# Half_H-Bridge_Driver.net
KiCad netlist of a schematic drawn in Altium Designer
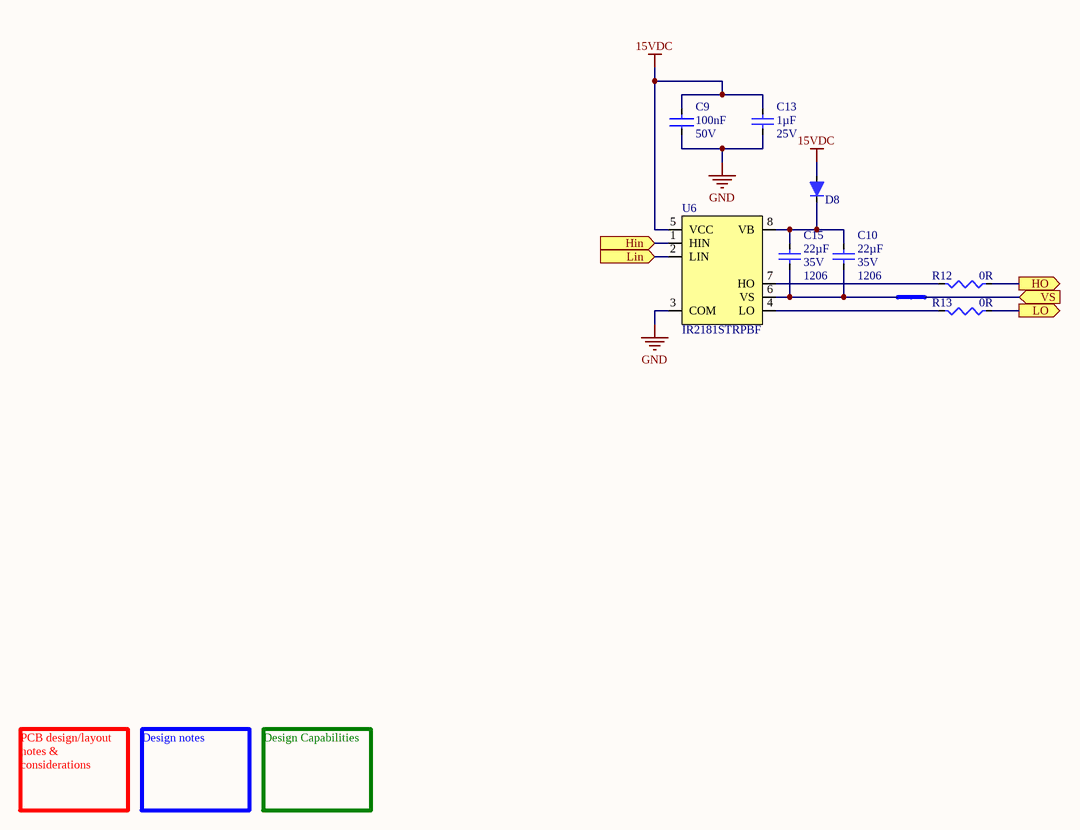
[diagram p0: Half H-Bridge Driver.SchDoc]

(export (version "E")
  (design (tool "Eeschema 10.0.6"))
  (components
    (comp (ref "C9")
      (value "100nF 0603 50V")
      (footprint "C0603 - Ceramic")
      (fields
        (field (name "MANUFACTURER") "Samsung Electro-Mechanics America, Inc")
        (field (name "MANUFACTURER PART NUMBER") "CL10B104KB8SFNC")
        (field (name "TOLERANCE") "±10%")
        (field (name "VOLTAGE - RATED") "50V")
        (field (name "CAPACITANCE") "100nF")
      )
      (libsource (lib "Personal Library") (part "100nF 0603 50V"))
    )
    (comp (ref "C10")
      (value "22uF 1206 35V")
      (description "Non-polarized")
      (fields
        (field (name "MANUFACTURER") "TDK Corporation")
        (field (name "MANUFACTURER PART NUMBER") "C3216X5R1V226M160AC")
        (field (name "CAPACITANCE") "22µF")
        (field (name "VOLTAGE - RATED") "35V")
        (field (name "PACKAGE / CASE") "1206")
      )
      (libsource (lib "Local Library") (part "22uF 1206 35V"))
    )
    (comp (ref "C13")
      (value "1uF 0603 25V")
      (footprint "Capacitor - 0603 Ceramic")
      (description "Non-polarized")
      (fields
        (field (name "MANUFACTURER") "Murata Electronics North America")
        (field (name "MANUFACTURER PART NUMBER") "GRM188R61E105KA12D")
        (field (name "VOLTAGE - RATED") "25V")
        (field (name "CAPACITANCE") "1µF")
      )
      (libsource (lib "Local Library") (part "1uF 0603 25V"))
    )
    (comp (ref "C15")
      (value "22uF 1206 35V")
      (description "Non-polarized")
      (fields
        (field (name "MANUFACTURER") "TDK Corporation")
        (field (name "MANUFACTURER PART NUMBER") "C3216X5R1V226M160AC")
        (field (name "VOLTAGE - RATED") "35V")
        (field (name "PACKAGE / CASE") "1206")
        (field (name "CAPACITANCE") "22µF")
      )
      (libsource (lib "Local Library") (part "22uF 1206 35V"))
    )
    (comp (ref "D8")
      (value "~")
      (description "Signal Diode")
      (fields
        (field (name "MANUFACTURER") "Vishay Semiconductor Diodes Division")
        (field (name "MANUFACTURER PART NUMBER") "US1G-E3/5AT")
      )
      (libsource (lib "Local Library") (part "Diode - Signal 1A"))
    )
    (comp (ref "NetTie1")
      (value "Net Tie - Same Size")
      (description "Ties two nets together")
      (libsource (lib "Local Library") (part "Net Tie - Same Size"))
    )
    (comp (ref "R12")
      (value "0R 0603")
      (footprint "R0603")
      (fields
        (field (name "MANUFACTURER") "Yageo")
        (field (name "MANUFACTURER PART NUMBER") "RC0603JR-070RL")
        (field (name "RESISTANCE (OHMS)") "0R")
        (field (name "TOLERANCE") "Jumper")
      )
      (libsource (lib "Local Library") (part "0R 0603"))
    )
    (comp (ref "R13")
      (value "0R 0603")
      (footprint "R0603")
      (fields
        (field (name "MANUFACTURER") "Yageo")
        (field (name "MANUFACTURER PART NUMBER") "RC0603JR-070RL")
        (field (name "RESISTANCE (OHMS)") "0R")
        (field (name "TOLERANCE") "Jumper")
      )
      (libsource (lib "Local Library") (part "0R 0603"))
    )
    (comp (ref "U6")
      (value "H-Bridge Driver")
      (footprint "SOIC-8")
      (fields
        (field (name "MANUFACTURER") "Infineon Technologies")
        (field (name "MANUFACTURER PART NUMBER") "IR2181STRPBF")
      )
      (libsource (lib "Local Library") (part "H-Bridge Driver"))
    )
  )
  (nets
    (net (code "1") (name "/HO") (class "Default")
      (node (ref "R12") (pin "2") (pinfunction "2_2") (pintype "passive"))
    )
    (net (code "2") (name "/Hin") (class "Default")
      (node (ref "U6") (pin "1") (pinfunction "HIN_1") (pintype "passive"))
    )
    (net (code "3") (name "/LO") (class "Default")
      (node (ref "R13") (pin "2") (pinfunction "2_2") (pintype "passive"))
    )
    (net (code "4") (name "/Lin") (class "Default")
      (node (ref "U6") (pin "2") (pinfunction "LIN_2") (pintype "passive"))
    )
    (net (code "5") (name "/VS") (class "Default")
      (node (ref "NetTie1") (pin "1") (pinfunction "1_1") (pintype "passive"))
    )
    (net (code "6") (name "15VDC") (class "Default")
      (node (ref "C13") (pin "1") (pinfunction "1_1") (pintype "passive"))
      (node (ref "C9") (pin "1") (pinfunction "1_1") (pintype "passive"))
      (node (ref "D8") (pin "1") (pinfunction "Anode_1") (pintype "passive"))
      (node (ref "U6") (pin "5") (pinfunction "VCC_5") (pintype "passive"))
    )
    (net (code "7") (name "GND") (class "Default")
      (node (ref "C13") (pin "2") (pinfunction "2_2") (pintype "passive"))
      (node (ref "C9") (pin "2") (pinfunction "2_2") (pintype "passive"))
      (node (ref "U6") (pin "3") (pinfunction "COM_3") (pintype "passive"))
    )
    (net (code "8") (name "Net-(D8-Cathode)") (class "Default")
      (node (ref "C10") (pin "1") (pinfunction "1_1") (pintype "passive"))
      (node (ref "C15") (pin "1") (pinfunction "1_1") (pintype "passive"))
      (node (ref "D8") (pin "2") (pinfunction "Cathode_2") (pintype "passive"))
      (node (ref "U6") (pin "8") (pinfunction "VB_8") (pintype "passive"))
    )
    (net (code "9") (name "Net-(U6-HO)") (class "Default")
      (node (ref "R12") (pin "1") (pinfunction "1_1") (pintype "passive"))
      (node (ref "U6") (pin "7") (pinfunction "HO_7") (pintype "passive"))
    )
    (net (code "10") (name "Net-(U6-LO)") (class "Default")
      (node (ref "R13") (pin "1") (pinfunction "1_1") (pintype "passive"))
      (node (ref "U6") (pin "4") (pinfunction "LO_4") (pintype "passive"))
    )
    (net (code "11") (name "Net-(U6-VS)") (class "Default")
      (node (ref "C10") (pin "2") (pinfunction "2_2") (pintype "passive"))
      (node (ref "C15") (pin "2") (pinfunction "2_2") (pintype "passive"))
      (node (ref "NetTie1") (pin "2") (pinfunction "2_2") (pintype "passive"))
      (node (ref "U6") (pin "6") (pinfunction "VS_6") (pintype "passive"))
    )
  )
)
